# SmartSwitch3.net
KiCad netlist of a schematic drawn in EAGLE
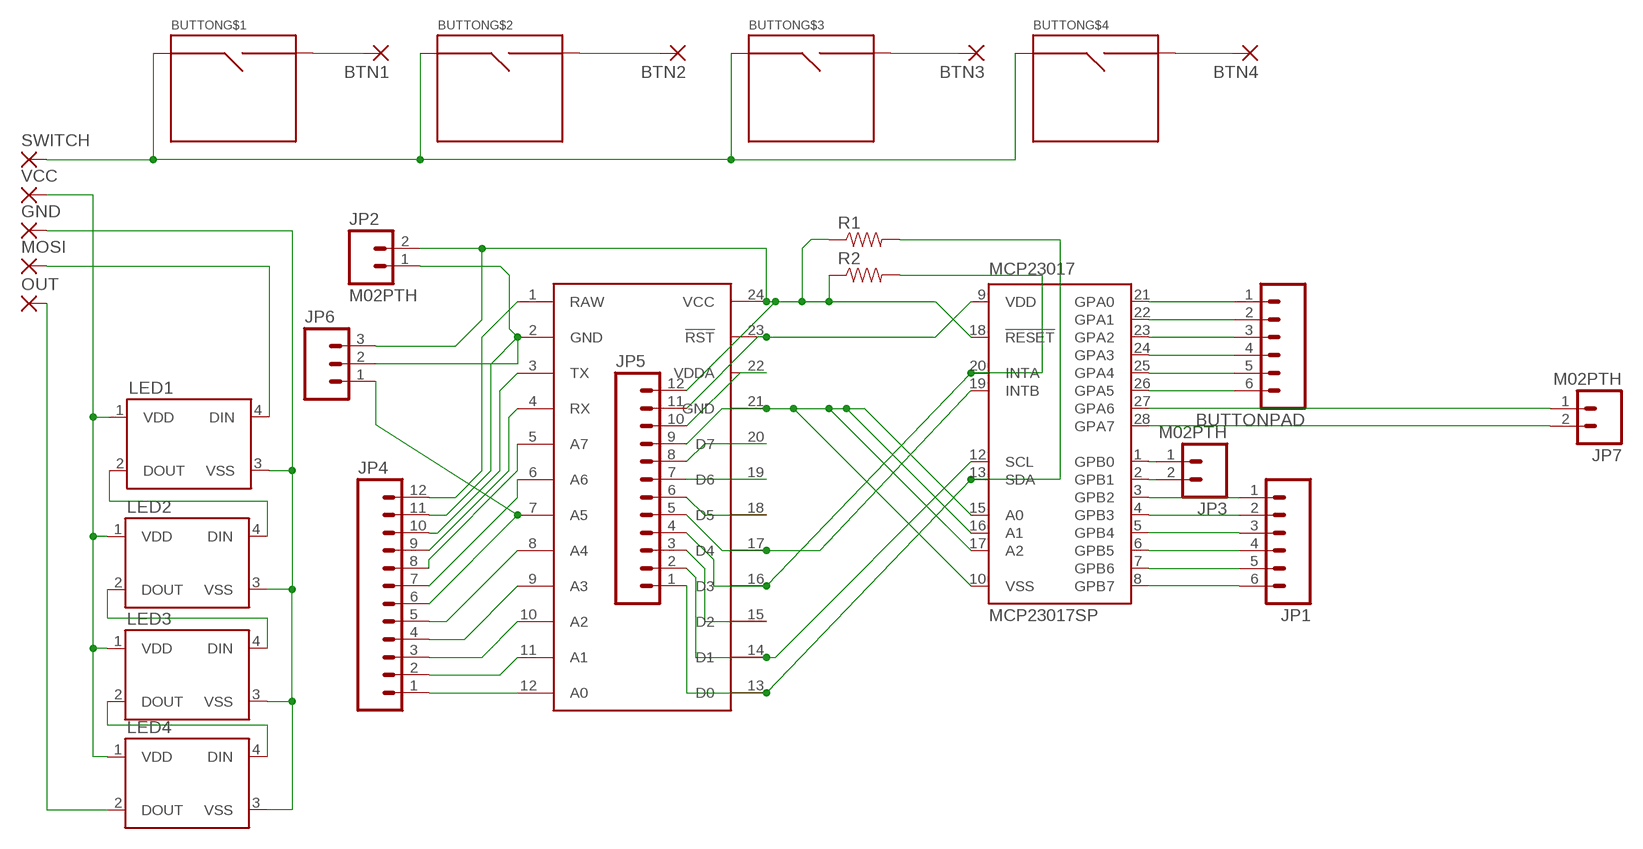
[diagram p0: schematic, sheet 1]

(export (version "E")
  (design (tool "Eeschema 10.0.6"))
  (components
    (comp (ref "BTN1")
      (value "2,15/1,0")
      (footprint "eagle-import:2,15_1,0")
      (libsource (lib "eagle-import") (part "2,15/1,0"))
    )
    (comp (ref "BTN2")
      (value "2,15/1,0")
      (footprint "eagle-import:2,15_1,0")
      (libsource (lib "eagle-import") (part "2,15/1,0"))
    )
    (comp (ref "BTN3")
      (value "2,15/1,0")
      (footprint "eagle-import:2,15_1,0")
      (libsource (lib "eagle-import") (part "2,15/1,0"))
    )
    (comp (ref "BTN4")
      (value "2,15/1,0")
      (footprint "eagle-import:2,15_1,0")
      (libsource (lib "eagle-import") (part "2,15/1,0"))
    )
    (comp (ref "BUTTON")
      (value "BUTTON")
      (footprint "eagle-import:BUTTON")
      (libsource (lib "eagle-import") (part "BUTTON"))
    )
    (comp (ref "BUTTONPAD")
      (value "M06SILK_FEMALE_PTH")
      (footprint "eagle-import:1X06")
      (libsource (lib "eagle-import") (part "M06SILK_FEMALE_PTH"))
    )
    (comp (ref "GND")
      (value "2,15/1,0")
      (footprint "eagle-import:2,15_1,0")
      (libsource (lib "eagle-import") (part "2,15/1,0"))
    )
    (comp (ref "JP1")
      (value "M06SILK_FEMALE_PTH")
      (footprint "eagle-import:1X06")
      (libsource (lib "eagle-import") (part "M06SILK_FEMALE_PTH"))
    )
    (comp (ref "JP2")
      (value "M02PTH")
      (footprint "eagle-import:1X02")
      (libsource (lib "eagle-import") (part "M02PTH"))
    )
    (comp (ref "JP3")
      (value "M02PTH")
      (footprint "eagle-import:1X02")
      (libsource (lib "eagle-import") (part "M02PTH"))
    )
    (comp (ref "JP4")
      (value "M12PTH")
      (footprint "eagle-import:1X12-SMALL-PADS")
      (libsource (lib "eagle-import") (part "M12PTH"))
    )
    (comp (ref "JP5")
      (value "M12PTH")
      (footprint "eagle-import:1X12-SMALL-PADS")
      (libsource (lib "eagle-import") (part "M12PTH"))
    )
    (comp (ref "JP6")
      (value "M03PTH")
      (footprint "eagle-import:1X03")
      (libsource (lib "eagle-import") (part "M03PTH"))
    )
    (comp (ref "JP7")
      (value "M02PTH")
      (footprint "eagle-import:1X02")
      (libsource (lib "eagle-import") (part "M02PTH"))
    )
    (comp (ref "LED1")
      (value "WS2812B")
      (footprint "eagle-import:WS2812B")
      (libsource (lib "eagle-import") (part "WS2812B"))
    )
    (comp (ref "LED2")
      (value "WS2812B")
      (footprint "eagle-import:WS2812B")
      (libsource (lib "eagle-import") (part "WS2812B"))
    )
    (comp (ref "LED3")
      (value "WS2812B")
      (footprint "eagle-import:WS2812B")
      (libsource (lib "eagle-import") (part "WS2812B"))
    )
    (comp (ref "LED4")
      (value "WS2812B")
      (footprint "eagle-import:WS2812B")
      (libsource (lib "eagle-import") (part "WS2812B"))
    )
    (comp (ref "MCP23017")
      (value "MCP23017SP")
      (footprint "eagle-import:DIL28-3")
      (libsource (lib "eagle-import") (part "MCP23017SP"))
    )
    (comp (ref "MOSI")
      (value "2,15/1,0")
      (footprint "eagle-import:2,15_1,0")
      (libsource (lib "eagle-import") (part "2,15/1,0"))
    )
    (comp (ref "OUT")
      (value "2,15/1,0")
      (footprint "eagle-import:2,15_1,0")
      (libsource (lib "eagle-import") (part "2,15/1,0"))
    )
    (comp (ref "R1")
      (value "RESISTORPTH-1/2W")
      (footprint "eagle-import:AXIAL-0.5")
      (libsource (lib "eagle-import") (part "RESISTORPTH-1/2W"))
    )
    (comp (ref "R2")
      (value "RESISTORPTH-1/2W")
      (footprint "eagle-import:AXIAL-0.5")
      (libsource (lib "eagle-import") (part "RESISTORPTH-1/2W"))
    )
    (comp (ref "SPARK")
      (value "SPARK_CORECORE")
      (footprint "eagle-import:SPARK_CORE")
      (libsource (lib "eagle-import") (part "SPARK_CORECORE"))
    )
    (comp (ref "SWITCH")
      (value "2,15/1,0")
      (footprint "eagle-import:2,15_1,0")
      (libsource (lib "eagle-import") (part "2,15/1,0"))
    )
    (comp (ref "VCC")
      (value "2,15/1,0")
      (footprint "eagle-import:2,15_1,0")
      (libsource (lib "eagle-import") (part "2,15/1,0"))
    )
  )
  (nets
    (net (code "1") (name "Net-(BTN1-P)") (class "Default")
      (node (ref "BTN1") (pin "1") (pinfunction "P_1") (pintype "passive"))
      (node (ref "BUTTON") (pin "SIG2") (pinfunction "SIG2_SIG2") (pintype "bidirectional"))
    )
    (net (code "2") (name "Net-(BTN2-P)") (class "Default")
      (node (ref "BTN2") (pin "1") (pinfunction "P_1") (pintype "passive"))
      (node (ref "BUTTON") (pin "SIG4") (pinfunction "SIG2_SIG4") (pintype "bidirectional"))
    )
    (net (code "3") (name "Net-(BTN3-P)") (class "Default")
      (node (ref "BTN3") (pin "1") (pinfunction "P_1") (pintype "passive"))
      (node (ref "BUTTON") (pin "SIG6") (pinfunction "SIG2_SIG6") (pintype "bidirectional"))
    )
    (net (code "4") (name "Net-(BTN4-P)") (class "Default")
      (node (ref "BTN4") (pin "1") (pinfunction "P_1") (pintype "passive"))
      (node (ref "BUTTON") (pin "SIG8") (pinfunction "SIG2_SIG8") (pintype "bidirectional"))
    )
    (net (code "5") (name "Net-(BUTTONB-SIG1)") (class "Default")
      (node (ref "BUTTON") (pin "SIG1") (pinfunction "SIG1_SIG1") (pintype "bidirectional"))
      (node (ref "BUTTON") (pin "SIG3") (pinfunction "SIG1_SIG3") (pintype "bidirectional"))
      (node (ref "BUTTON") (pin "SIG5") (pinfunction "SIG1_SIG5") (pintype "bidirectional"))
      (node (ref "BUTTON") (pin "SIG7") (pinfunction "SIG1_SIG7") (pintype "bidirectional"))
      (node (ref "SWITCH") (pin "1") (pinfunction "P_1") (pintype "passive"))
    )
    (net (code "6") (name "Net-(GND-P)") (class "Default")
      (node (ref "GND") (pin "1") (pinfunction "P_1") (pintype "passive"))
      (node (ref "LED1") (pin "3") (pinfunction "VSS_3") (pintype "power_in"))
      (node (ref "LED2") (pin "3") (pinfunction "VSS_3") (pintype "power_in"))
      (node (ref "LED3") (pin "3") (pinfunction "VSS_3") (pintype "power_in"))
      (node (ref "LED4") (pin "3") (pinfunction "VSS_3") (pintype "power_in"))
    )
    (net (code "7") (name "Net-(JP2-Pad1)") (class "Default")
      (node (ref "JP2") (pin "1") (pinfunction "1_1") (pintype "passive"))
      (node (ref "JP4") (pin "11") (pinfunction "11_11") (pintype "passive"))
      (node (ref "JP6") (pin "2") (pinfunction "2_2") (pintype "passive"))
      (node (ref "SPARK") (pin "2") (pinfunction "GND_2") (pintype "power_in"))
    )
    (net (code "8") (name "Net-(LED1-DIN)") (class "Default")
      (node (ref "LED1") (pin "4") (pinfunction "DIN_4") (pintype "input"))
      (node (ref "MOSI") (pin "1") (pinfunction "P_1") (pintype "passive"))
    )
    (net (code "9") (name "Net-(LED1-DOUT)") (class "Default")
      (node (ref "LED1") (pin "2") (pinfunction "DOUT_2") (pintype "output"))
      (node (ref "LED2") (pin "4") (pinfunction "DIN_4") (pintype "input"))
    )
    (net (code "10") (name "Net-(LED1-VDD)") (class "Default")
      (node (ref "LED1") (pin "1") (pinfunction "VDD_1") (pintype "power_in"))
      (node (ref "LED2") (pin "1") (pinfunction "VDD_1") (pintype "power_in"))
      (node (ref "LED3") (pin "1") (pinfunction "VDD_1") (pintype "power_in"))
      (node (ref "LED4") (pin "1") (pinfunction "VDD_1") (pintype "power_in"))
      (node (ref "VCC") (pin "1") (pinfunction "P_1") (pintype "passive"))
    )
    (net (code "11") (name "Net-(LED2-DOUT)") (class "Default")
      (node (ref "LED2") (pin "2") (pinfunction "DOUT_2") (pintype "output"))
      (node (ref "LED3") (pin "4") (pinfunction "DIN_4") (pintype "input"))
    )
    (net (code "12") (name "Net-(LED3-DOUT)") (class "Default")
      (node (ref "LED3") (pin "2") (pinfunction "DOUT_2") (pintype "output"))
      (node (ref "LED4") (pin "4") (pinfunction "DIN_4") (pintype "input"))
    )
    (net (code "13") (name "Net-(LED4-DOUT)") (class "Default")
      (node (ref "LED4") (pin "2") (pinfunction "DOUT_2") (pintype "output"))
      (node (ref "OUT") (pin "1") (pinfunction "P_1") (pintype "passive"))
    )
    (net (code "14") (name "Net-(MCP23017-A0)") (class "Default")
      (node (ref "JP5") (pin "9") (pinfunction "9_9") (pintype "passive"))
      (node (ref "MCP23017") (pin "10") (pinfunction "VSS_10") (pintype "power_in"))
      (node (ref "MCP23017") (pin "15") (pinfunction "A0_15") (pintype "input"))
      (node (ref "MCP23017") (pin "16") (pinfunction "A1_16") (pintype "input"))
      (node (ref "MCP23017") (pin "17") (pinfunction "A2_17") (pintype "input"))
      (node (ref "SPARK") (pin "21") (pinfunction "GND_21") (pintype "power_in"))
    )
    (net (code "15") (name "Net-(MCP23017-GPA0)") (class "Default")
      (node (ref "BUTTONPAD") (pin "1") (pinfunction "1_1") (pintype "passive"))
      (node (ref "MCP23017") (pin "21") (pinfunction "GPA0_21") (pintype "bidirectional"))
    )
    (net (code "16") (name "Net-(MCP23017-GPA1)") (class "Default")
      (node (ref "BUTTONPAD") (pin "2") (pinfunction "2_2") (pintype "passive"))
      (node (ref "MCP23017") (pin "22") (pinfunction "GPA1_22") (pintype "bidirectional"))
    )
    (net (code "17") (name "Net-(MCP23017-GPA2)") (class "Default")
      (node (ref "BUTTONPAD") (pin "3") (pinfunction "3_3") (pintype "passive"))
      (node (ref "MCP23017") (pin "23") (pinfunction "GPA2_23") (pintype "bidirectional"))
    )
    (net (code "18") (name "Net-(MCP23017-GPA3)") (class "Default")
      (node (ref "BUTTONPAD") (pin "4") (pinfunction "4_4") (pintype "passive"))
      (node (ref "MCP23017") (pin "24") (pinfunction "GPA3_24") (pintype "bidirectional"))
    )
    (net (code "19") (name "Net-(MCP23017-GPA4)") (class "Default")
      (node (ref "BUTTONPAD") (pin "5") (pinfunction "5_5") (pintype "passive"))
      (node (ref "MCP23017") (pin "25") (pinfunction "GPA4_25") (pintype "bidirectional"))
    )
    (net (code "20") (name "Net-(MCP23017-GPA5)") (class "Default")
      (node (ref "BUTTONPAD") (pin "6") (pinfunction "6_6") (pintype "passive"))
      (node (ref "MCP23017") (pin "26") (pinfunction "GPA5_26") (pintype "bidirectional"))
    )
    (net (code "21") (name "Net-(MCP23017-GPA6)") (class "Default")
      (node (ref "JP7") (pin "1") (pinfunction "1_1") (pintype "passive"))
      (node (ref "MCP23017") (pin "27") (pinfunction "GPA6_27") (pintype "bidirectional"))
    )
    (net (code "22") (name "Net-(MCP23017-GPA7)") (class "Default")
      (node (ref "JP7") (pin "2") (pinfunction "2_2") (pintype "passive"))
      (node (ref "MCP23017") (pin "28") (pinfunction "GPA7_28") (pintype "bidirectional"))
    )
    (net (code "23") (name "Net-(MCP23017-GPB0)") (class "Default")
      (node (ref "JP3") (pin "1") (pinfunction "1_1") (pintype "passive"))
      (node (ref "MCP23017") (pin "1") (pinfunction "GPB0_1") (pintype "bidirectional"))
    )
    (net (code "24") (name "Net-(MCP23017-GPB1)") (class "Default")
      (node (ref "JP3") (pin "2") (pinfunction "2_2") (pintype "passive"))
      (node (ref "MCP23017") (pin "2") (pinfunction "GPB1_2") (pintype "bidirectional"))
    )
    (net (code "25") (name "Net-(MCP23017-GPB2)") (class "Default")
      (node (ref "JP1") (pin "1") (pinfunction "1_1") (pintype "passive"))
      (node (ref "MCP23017") (pin "3") (pinfunction "GPB2_3") (pintype "bidirectional"))
    )
    (net (code "26") (name "Net-(MCP23017-GPB3)") (class "Default")
      (node (ref "JP1") (pin "2") (pinfunction "2_2") (pintype "passive"))
      (node (ref "MCP23017") (pin "4") (pinfunction "GPB3_4") (pintype "bidirectional"))
    )
    (net (code "27") (name "Net-(MCP23017-GPB4)") (class "Default")
      (node (ref "JP1") (pin "3") (pinfunction "3_3") (pintype "passive"))
      (node (ref "MCP23017") (pin "5") (pinfunction "GPB4_5") (pintype "bidirectional"))
    )
    (net (code "28") (name "Net-(MCP23017-GPB5)") (class "Default")
      (node (ref "JP1") (pin "4") (pinfunction "4_4") (pintype "passive"))
      (node (ref "MCP23017") (pin "6") (pinfunction "GPB5_6") (pintype "bidirectional"))
    )
    (net (code "29") (name "Net-(MCP23017-GPB6)") (class "Default")
      (node (ref "JP1") (pin "5") (pinfunction "5_5") (pintype "passive"))
      (node (ref "MCP23017") (pin "7") (pinfunction "GPB6_7") (pintype "bidirectional"))
    )
    (net (code "30") (name "Net-(MCP23017-GPB7)") (class "Default")
      (node (ref "JP1") (pin "6") (pinfunction "6_6") (pintype "passive"))
      (node (ref "MCP23017") (pin "8") (pinfunction "GPB7_8") (pintype "bidirectional"))
    )
    (net (code "31") (name "Net-(MCP23017-INTA)") (class "Default")
      (node (ref "JP5") (pin "4") (pinfunction "4_4") (pintype "passive"))
      (node (ref "MCP23017") (pin "20") (pinfunction "INTA_20") (pintype "output"))
      (node (ref "R2") (pin "P$2") (pinfunction "2_P$2") (pintype "passive"))
      (node (ref "SPARK") (pin "16") (pinfunction "D3_16") (pintype "bidirectional"))
    )
    (net (code "32") (name "Net-(MCP23017-INTB)") (class "Default")
      (node (ref "JP5") (pin "5") (pinfunction "5_5") (pintype "passive"))
      (node (ref "MCP23017") (pin "19") (pinfunction "INTB_19") (pintype "output"))
      (node (ref "SPARK") (pin "17") (pinfunction "D4_17") (pintype "bidirectional"))
    )
    (net (code "33") (name "Net-(MCP23017-SCL)") (class "Default")
      (node (ref "JP5") (pin "2") (pinfunction "2_2") (pintype "passive"))
      (node (ref "MCP23017") (pin "12") (pinfunction "SCL_12") (pintype "input"))
      (node (ref "SPARK") (pin "14") (pinfunction "D1_14") (pintype "bidirectional"))
    )
    (net (code "34") (name "Net-(MCP23017-SDA)") (class "Default")
      (node (ref "JP5") (pin "1") (pinfunction "1_1") (pintype "passive"))
      (node (ref "MCP23017") (pin "13") (pinfunction "SDA_13") (pintype "bidirectional"))
      (node (ref "R1") (pin "P$2") (pinfunction "2_P$2") (pintype "passive"))
      (node (ref "SPARK") (pin "13") (pinfunction "D0_13") (pintype "bidirectional"))
    )
    (net (code "35") (name "Net-(MCP23017-VDD)") (class "Default")
      (node (ref "JP5") (pin "11") (pinfunction "11_11") (pintype "passive"))
      (node (ref "MCP23017") (pin "9") (pinfunction "VDD_9") (pintype "power_in"))
      (node (ref "SPARK") (pin "23") (pinfunction "~{RST}_23") (pintype "bidirectional"))
    )
    (net (code "36") (name "Net-(MCP23017-~{RESET})") (class "Default")
      (node (ref "JP2") (pin "2") (pinfunction "2_2") (pintype "passive"))
      (node (ref "JP5") (pin "12") (pinfunction "12_12") (pintype "passive"))
      (node (ref "JP6") (pin "3") (pinfunction "3_3") (pintype "passive"))
      (node (ref "MCP23017") (pin "18") (pinfunction "~{RESET}_18") (pintype "input"))
      (node (ref "R1") (pin "P$1") (pinfunction "1_P$1") (pintype "passive"))
      (node (ref "R2") (pin "P$1") (pinfunction "1_P$1") (pintype "passive"))
      (node (ref "SPARK") (pin "24") (pinfunction "VCC_24") (pintype "power_in"))
    )
    (net (code "37") (name "Net-(SPARK-A0)") (class "Default")
      (node (ref "JP4") (pin "1") (pinfunction "1_1") (pintype "passive"))
      (node (ref "SPARK") (pin "12") (pinfunction "A0_12") (pintype "bidirectional"))
    )
    (net (code "38") (name "Net-(SPARK-A1)") (class "Default")
      (node (ref "JP4") (pin "2") (pinfunction "2_2") (pintype "passive"))
      (node (ref "SPARK") (pin "11") (pinfunction "A1_11") (pintype "bidirectional"))
    )
    (net (code "39") (name "Net-(SPARK-A2)") (class "Default")
      (node (ref "JP4") (pin "3") (pinfunction "3_3") (pintype "passive"))
      (node (ref "SPARK") (pin "10") (pinfunction "A2_10") (pintype "bidirectional"))
    )
    (net (code "40") (name "Net-(SPARK-A3)") (class "Default")
      (node (ref "JP4") (pin "4") (pinfunction "4_4") (pintype "passive"))
      (node (ref "SPARK") (pin "9") (pinfunction "A3_9") (pintype "bidirectional"))
    )
    (net (code "41") (name "Net-(SPARK-A4)") (class "Default")
      (node (ref "JP4") (pin "5") (pinfunction "5_5") (pintype "passive"))
      (node (ref "SPARK") (pin "8") (pinfunction "A4_8") (pintype "bidirectional"))
    )
    (net (code "42") (name "Net-(SPARK-A5)") (class "Default")
      (node (ref "JP4") (pin "6") (pinfunction "6_6") (pintype "passive"))
      (node (ref "JP6") (pin "1") (pinfunction "1_1") (pintype "passive"))
      (node (ref "SPARK") (pin "7") (pinfunction "A5_7") (pintype "bidirectional"))
    )
    (net (code "43") (name "Net-(SPARK-A6)") (class "Default")
      (node (ref "JP4") (pin "7") (pinfunction "7_7") (pintype "passive"))
      (node (ref "SPARK") (pin "6") (pinfunction "A6_6") (pintype "bidirectional"))
    )
    (net (code "44") (name "Net-(SPARK-A7)") (class "Default")
      (node (ref "JP4") (pin "8") (pinfunction "8_8") (pintype "passive"))
      (node (ref "SPARK") (pin "5") (pinfunction "A7_5") (pintype "bidirectional"))
    )
    (net (code "45") (name "Net-(SPARK-D2)") (class "Default")
      (node (ref "JP5") (pin "3") (pinfunction "3_3") (pintype "passive"))
      (node (ref "SPARK") (pin "15") (pinfunction "D2_15") (pintype "bidirectional"))
    )
    (net (code "46") (name "Net-(SPARK-D5)") (class "Default")
      (node (ref "JP5") (pin "6") (pinfunction "6_6") (pintype "passive"))
      (node (ref "SPARK") (pin "18") (pinfunction "D5_18") (pintype "bidirectional"))
    )
    (net (code "47") (name "Net-(SPARK-D6)") (class "Default")
      (node (ref "JP5") (pin "7") (pinfunction "7_7") (pintype "passive"))
      (node (ref "SPARK") (pin "19") (pinfunction "D6_19") (pintype "bidirectional"))
    )
    (net (code "48") (name "Net-(SPARK-D7)") (class "Default")
      (node (ref "JP5") (pin "8") (pinfunction "8_8") (pintype "passive"))
      (node (ref "SPARK") (pin "20") (pinfunction "D7_20") (pintype "bidirectional"))
    )
    (net (code "49") (name "Net-(SPARK-RAW)") (class "Default")
      (node (ref "JP4") (pin "12") (pinfunction "12_12") (pintype "passive"))
      (node (ref "SPARK") (pin "1") (pinfunction "RAW_1") (pintype "power_in"))
    )
    (net (code "50") (name "Net-(SPARK-RX)") (class "Default")
      (node (ref "JP4") (pin "9") (pinfunction "9_9") (pintype "passive"))
      (node (ref "SPARK") (pin "4") (pinfunction "RX_4") (pintype "bidirectional"))
    )
    (net (code "51") (name "Net-(SPARK-TX)") (class "Default")
      (node (ref "JP4") (pin "10") (pinfunction "10_10") (pintype "passive"))
      (node (ref "SPARK") (pin "3") (pinfunction "TX_3") (pintype "bidirectional"))
    )
    (net (code "52") (name "Net-(SPARK-VDDA)") (class "Default")
      (node (ref "JP5") (pin "10") (pinfunction "10_10") (pintype "passive"))
      (node (ref "SPARK") (pin "22") (pinfunction "VDDA_22") (pintype "power_in"))
    )
  )
)
